# fpga_peripherals.net
KiCad netlist of a schematic drawn in Altium Designer
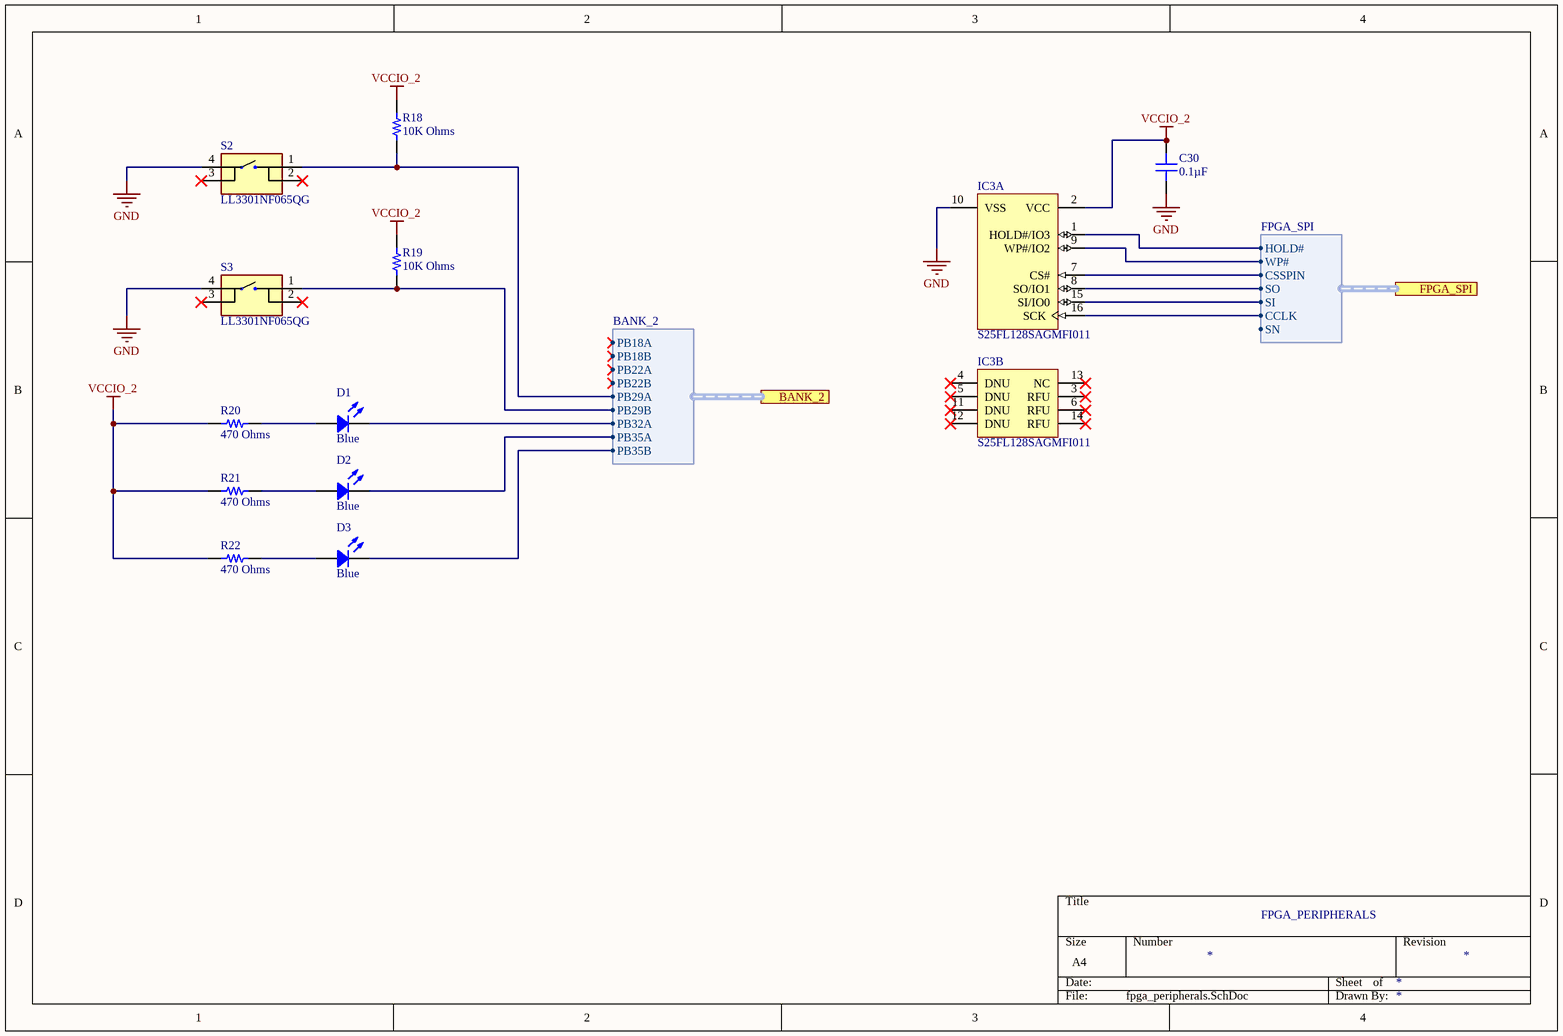
[diagram p0: fpga_peripherals.SchDoc]

(export (version "E")
  (design (tool "Eeschema 10.0.6"))
  (components
    (comp (ref "C30")
      (value "0.1µF")
      (footprint "CAP 0603_1608")
      (description "CAP CER 0.1UF 50V X7R 0603")
      (fields (field (name "PART NUMBER") "C0603C104K5RAC7411") (field (name "MANUFACTURER") "KEMET"))
      (libsource (lib "Celestial Altium Library - altium_library (2)") (part "Capacitor"))
    )
    (comp (ref "D1")
      (value "Blue")
      (footprint "LED 0603_1608 BLUE")
      (description "LED BLUE 0603 SMD")
      (fields
        (field (name "PART NUMBER") "VLMB1300-GS08")
        (field (name "MANUFACTURER") "Vishay Semiconductor Opto Division")
      )
      (libsource (lib "Celestial Altium Library - altium_library (2)") (part "LED"))
    )
    (comp (ref "D2")
      (value "Blue")
      (footprint "LED 0603_1608 BLUE")
      (description "LED BLUE 0603 SMD")
      (fields
        (field (name "PART NUMBER") "VLMB1300-GS08")
        (field (name "MANUFACTURER") "Vishay Semiconductor Opto Division")
      )
      (libsource (lib "Celestial Altium Library - altium_library (2)") (part "LED"))
    )
    (comp (ref "D3")
      (value "Blue")
      (footprint "LED 0603_1608 BLUE")
      (description "LED BLUE 0603 SMD")
      (fields
        (field (name "PART NUMBER") "VLMB1300-GS08")
        (field (name "MANUFACTURER") "Vishay Semiconductor Opto Division")
      )
      (libsource (lib "Celestial Altium Library - altium_library (2)") (part "LED"))
    )
    (comp (ref "IC3")
      (value "S25FL128SAGMFI011")
      (footprint "SPSN-SOIC-16_L")
      (fields (field (name "MANUFACTURER") "Spansion"))
      (libsource (lib "Altium Content Vault") (part "SPSN-S25FL128S-16"))
    )
    (comp (ref "R18")
      (value "10K Ohms")
      (footprint "RES 0603_1608")
      (description "RES SMD 470 OHM 5% 1/4W 0603")
      (fields (field (name "PART NUMBER") "CRCW0603470RJNEAHP") (field (name "MANUFACTURER") "Vishay Dale"))
      (libsource (lib "Celestial Altium Library - altium_library (2)") (part "Resistor"))
    )
    (comp (ref "R19")
      (value "10K Ohms")
      (footprint "RES 0603_1608")
      (description "RES SMD 470 OHM 5% 1/4W 0603")
      (fields (field (name "PART NUMBER") "CRCW0603470RJNEAHP") (field (name "MANUFACTURER") "Vishay Dale"))
      (libsource (lib "Celestial Altium Library - altium_library (2)") (part "Resistor"))
    )
    (comp (ref "R20")
      (value "470 Ohms")
      (footprint "RES 0603_1608")
      (description "RES SMD 470 OHM 5% 1/4W 0603")
      (fields (field (name "PART NUMBER") "CRCW0603470RJNEAHP") (field (name "MANUFACTURER") "Vishay Dale"))
      (libsource (lib "Celestial Altium Library - altium_library (2)") (part "Resistor"))
    )
    (comp (ref "R21")
      (value "470 Ohms")
      (footprint "RES 0603_1608")
      (description "RES SMD 470 OHM 5% 1/4W 0603")
      (fields (field (name "PART NUMBER") "CRCW0603470RJNEAHP") (field (name "MANUFACTURER") "Vishay Dale"))
      (libsource (lib "Celestial Altium Library - altium_library (2)") (part "Resistor"))
    )
    (comp (ref "R22")
      (value "470 Ohms")
      (footprint "RES 0603_1608")
      (description "RES SMD 470 OHM 5% 1/4W 0603")
      (fields (field (name "PART NUMBER") "CRCW0603470RJNEAHP") (field (name "MANUFACTURER") "Vishay Dale"))
      (libsource (lib "Celestial Altium Library - altium_library (2)") (part "Resistor"))
    )
    (comp (ref "S2")
      (value "LL3301NF065QG")
      (footprint "SamacSys:LL3301NF065QG")
      (description "Switch")
      (fields (field (name "MOUSER PART NUMBER") "612-LL3301NF065QG"))
      (libsource (lib "SamacSys") (part "LL3301NF065QG"))
    )
    (comp (ref "S3")
      (value "LL3301NF065QG")
      (footprint "SamacSys:LL3301NF065QG")
      (description "Switch")
      (fields (field (name "MOUSER PART NUMBER") "612-LL3301NF065QG"))
      (libsource (lib "SamacSys") (part "LL3301NF065QG"))
    )
  )
  (nets
    (net (code "3") (name "/CCLK") (class "Default")
      (node (ref "IC3") (pin "16") (pinfunction "SCK_16") (pintype "input"))
    )
    (net (code "4") (name "/CSSPIN") (class "Default")
      (node (ref "IC3") (pin "7") (pinfunction "CS#_7") (pintype "input"))
    )
    (net (code "5") (name "/HOLD#") (class "Default")
      (node (ref "IC3") (pin "1") (pinfunction "HOLD#/IO3_1") (pintype "bidirectional"))
    )
    (net (code "6") (name "/PB29A") (class "Default")
      (node (ref "R18") (pin "1") (pinfunction "1_1") (pintype "passive"))
      (node (ref "S2") (pin "1") (pinfunction "1_1") (pintype "passive"))
    )
    (net (code "7") (name "/PB29B") (class "Default")
      (node (ref "R19") (pin "1") (pinfunction "1_1") (pintype "passive"))
      (node (ref "S3") (pin "1") (pinfunction "1_1") (pintype "passive"))
    )
    (net (code "8") (name "/PB32A") (class "Default")
      (node (ref "D1") (pin "2") (pinfunction "2_2") (pintype "passive"))
    )
    (net (code "9") (name "/PB35A") (class "Default")
      (node (ref "D2") (pin "2") (pinfunction "2_2") (pintype "passive"))
    )
    (net (code "10") (name "/PB35B") (class "Default")
      (node (ref "D3") (pin "2") (pinfunction "2_2") (pintype "passive"))
    )
    (net (code "11") (name "/SI") (class "Default")
      (node (ref "IC3") (pin "15") (pinfunction "SI/IO0_15") (pintype "bidirectional"))
    )
    (net (code "12") (name "/SO") (class "Default")
      (node (ref "IC3") (pin "8") (pinfunction "SO/IO1_8") (pintype "bidirectional"))
    )
    (net (code "13") (name "/WP#") (class "Default")
      (node (ref "IC3") (pin "9") (pinfunction "WP#/IO2_9") (pintype "bidirectional"))
    )
    (net (code "16") (name "GND") (class "Default")
      (node (ref "C30") (pin "1") (pinfunction "1_1") (pintype "passive"))
      (node (ref "IC3") (pin "10") (pinfunction "VSS_10") (pintype "power_in"))
      (node (ref "S2") (pin "4") (pinfunction "4_4") (pintype "passive"))
      (node (ref "S3") (pin "4") (pinfunction "4_4") (pintype "passive"))
    )
    (net (code "17") (name "Net-(D1-Pad1)") (class "Default")
      (node (ref "D1") (pin "1") (pinfunction "1_1") (pintype "passive"))
      (node (ref "R20") (pin "2") (pinfunction "2_2") (pintype "passive"))
    )
    (net (code "18") (name "Net-(D2-Pad1)") (class "Default")
      (node (ref "D2") (pin "1") (pinfunction "1_1") (pintype "passive"))
      (node (ref "R21") (pin "2") (pinfunction "2_2") (pintype "passive"))
    )
    (net (code "19") (name "Net-(D3-Pad1)") (class "Default")
      (node (ref "D3") (pin "1") (pinfunction "1_1") (pintype "passive"))
      (node (ref "R22") (pin "2") (pinfunction "2_2") (pintype "passive"))
    )
    (net (code "20") (name "VCCIO_2") (class "Default")
      (node (ref "C30") (pin "2") (pinfunction "2_2") (pintype "passive"))
      (node (ref "IC3") (pin "2") (pinfunction "VCC_2") (pintype "power_in"))
      (node (ref "R18") (pin "2") (pinfunction "2_2") (pintype "passive"))
      (node (ref "R19") (pin "2") (pinfunction "2_2") (pintype "passive"))
      (node (ref "R20") (pin "1") (pinfunction "1_1") (pintype "passive"))
      (node (ref "R21") (pin "1") (pinfunction "1_1") (pintype "passive"))
      (node (ref "R22") (pin "1") (pinfunction "1_1") (pintype "passive"))
    )
    (net (code "21") (name "unconnected-(IC3B-DNU-Pad4)") (class "Default")
      (node (ref "IC3") (pin "4") (pinfunction "DNU_4") (pintype "passive+no_connect"))
    )
    (net (code "22") (name "unconnected-(IC3B-DNU-Pad5)") (class "Default")
      (node (ref "IC3") (pin "5") (pinfunction "DNU_5") (pintype "passive+no_connect"))
    )
    (net (code "23") (name "unconnected-(IC3B-DNU-Pad11)") (class "Default")
      (node (ref "IC3") (pin "11") (pinfunction "DNU_11") (pintype "passive+no_connect"))
    )
    (net (code "24") (name "unconnected-(IC3B-DNU-Pad12)") (class "Default")
      (node (ref "IC3") (pin "12") (pinfunction "DNU_12") (pintype "passive+no_connect"))
    )
    (net (code "25") (name "unconnected-(IC3B-NC-Pad13)") (class "Default")
      (node (ref "IC3") (pin "13") (pinfunction "NC_13") (pintype "passive+no_connect"))
    )
    (net (code "26") (name "unconnected-(IC3B-RFU-Pad3)") (class "Default")
      (node (ref "IC3") (pin "3") (pinfunction "RFU_3") (pintype "passive+no_connect"))
    )
    (net (code "27") (name "unconnected-(IC3B-RFU-Pad6)") (class "Default")
      (node (ref "IC3") (pin "6") (pinfunction "RFU_6") (pintype "passive+no_connect"))
    )
    (net (code "28") (name "unconnected-(IC3B-RFU-Pad14)") (class "Default")
      (node (ref "IC3") (pin "14") (pinfunction "RFU_14") (pintype "passive+no_connect"))
    )
    (net (code "29") (name "unconnected-(S2-Pad2)") (class "Default")
      (node (ref "S2") (pin "2") (pinfunction "2_2") (pintype "passive+no_connect"))
    )
    (net (code "30") (name "unconnected-(S2-Pad3)") (class "Default")
      (node (ref "S2") (pin "3") (pinfunction "3_3") (pintype "passive+no_connect"))
    )
    (net (code "31") (name "unconnected-(S3-Pad2)") (class "Default")
      (node (ref "S3") (pin "2") (pinfunction "2_2") (pintype "passive+no_connect"))
    )
    (net (code "32") (name "unconnected-(S3-Pad3)") (class "Default")
      (node (ref "S3") (pin "3") (pinfunction "3_3") (pintype "passive+no_connect"))
    )
  )
)
